# lichten.net
KiCad netlist of a schematic drawn in Altium Designer
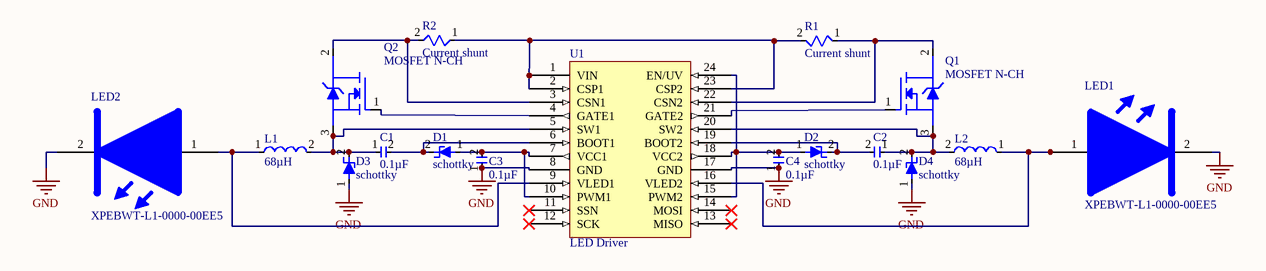
[diagram p0: lichten.SchDoc]

(export (version "E")
  (design (tool "Eeschema 10.0.6"))
  (components
    (comp (ref "C1")
      (value "0.1µF")
      (footprint "RC1206")
      (description "Cap Ceramic 0.1uF 50V X7R 10% SMD 2.0 x 1.2 mm 125 C Paper T/R")
      (fields
        (field (name "MANUFACTURER") "KEMET")
        (field (name "MANUFACTURER PART NUMBER") "C0805C104K5RACTU")
      )
      (libsource (lib "Lichten") (part "C0805C104K5RACTU"))
    )
    (comp (ref "C2")
      (value "0.1µF")
      (footprint "RC1206")
      (description "Cap Ceramic 0.1uF 50V X7R 10% SMD 2.0 x 1.2 mm 125 C Paper T/R")
      (fields
        (field (name "MANUFACTURER") "KEMET")
        (field (name "MANUFACTURER PART NUMBER") "C0805C104K5RACTU")
      )
      (libsource (lib "Lichten") (part "C0805C104K5RACTU"))
    )
    (comp (ref "C3")
      (value "0.1µF")
      (footprint "RC1206")
      (description "Cap Ceramic 0.1uF 50V X7R 10% SMD 2.0 x 1.2 mm 125 C Paper T/R")
      (fields
        (field (name "MANUFACTURER") "KEMET")
        (field (name "MANUFACTURER PART NUMBER") "C0805C104K5RACTU")
      )
      (libsource (lib "Lichten") (part "C0805C104K5RACTU"))
    )
    (comp (ref "C4")
      (value "0.1µF")
      (footprint "RC1206")
      (description "Cap Ceramic 0.1uF 50V X7R 10% SMD 2.0 x 1.2 mm 125 C Paper T/R")
      (fields
        (field (name "MANUFACTURER") "KEMET")
        (field (name "MANUFACTURER PART NUMBER") "C0805C104K5RACTU")
      )
      (libsource (lib "Lichten") (part "C0805C104K5RACTU"))
    )
    (comp (ref "D1")
      (value "schottky")
      (footprint "PMEG3050EP,115")
      (description "NEXPERIA - PMEG3050EP,115 - Schottky-likriktare, 30 V, 5 A, Enkel, SOD-128, 2 Stift, 360 mV")
      (fields
        (field (name "MANUFACTURER") "Nexperia USA")
        (field (name "MANUFACTURER PART NUMBER") "PMEG3050EP,115")
      )
      (libsource (lib "Lichten") (part "PMEG3050EP,115"))
    )
    (comp (ref "D2")
      (value "schottky")
      (footprint "PMEG3050EP,115")
      (description "NEXPERIA - PMEG3050EP,115 - Schottky-likriktare, 30 V, 5 A, Enkel, SOD-128, 2 Stift, 360 mV")
      (fields
        (field (name "MANUFACTURER") "Nexperia USA")
        (field (name "MANUFACTURER PART NUMBER") "PMEG3050EP,115")
      )
      (libsource (lib "Lichten") (part "PMEG3050EP,115"))
    )
    (comp (ref "D3")
      (value "schottky")
      (footprint "PMEG3050EP,115")
      (description "NEXPERIA - PMEG3050EP,115 - Schottky-likriktare, 30 V, 5 A, Enkel, SOD-128, 2 Stift, 360 mV")
      (fields
        (field (name "MANUFACTURER") "Nexperia USA")
        (field (name "MANUFACTURER PART NUMBER") "PMEG3050EP,115")
      )
      (libsource (lib "Lichten") (part "PMEG3050EP,115"))
    )
    (comp (ref "D4")
      (value "schottky")
      (footprint "PMEG3050EP,115")
      (description "NEXPERIA - PMEG3050EP,115 - Schottky-likriktare, 30 V, 5 A, Enkel, SOD-128, 2 Stift, 360 mV")
      (fields
        (field (name "MANUFACTURER") "Nexperia USA")
        (field (name "MANUFACTURER PART NUMBER") "PMEG3050EP,115")
      )
      (libsource (lib "Lichten") (part "PMEG3050EP,115"))
    )
    (comp (ref "L1")
      (value "68µH")
      (footprint "SRR1210-680M")
      (description "BOURNS         SRR1210-680M.             INDUCTOR, SHIELDED, 68UH, 2.7A, SMD")
      (fields (field (name "MANUFACTURER") "Bourns") (field (name "MANUFACTURER PART NUMBER") "SRR1210-680M"))
      (libsource (lib "") (part "SRR1210-680M_1"))
    )
    (comp (ref "L2")
      (value "68µH")
      (footprint "SRR1210-680M")
      (description "BOURNS         SRR1210-680M.             INDUCTOR, SHIELDED, 68UH, 2.7A, SMD")
      (fields (field (name "MANUFACTURER") "Bourns") (field (name "MANUFACTURER PART NUMBER") "SRR1210-680M"))
      (libsource (lib "Lichten") (part "SRR1210-680M"))
    )
    (comp (ref "LED1")
      (value "XPEBWT-L1-0000-00EE5")
      (footprint "XPEBWT-L1-0000-00EE5")
      (description "LED, XLAMP, XP-E, NEUTRAL WHITE, 114LM")
      (fields (field (name "MANUFACTURER") "Cree"))
      (libsource (lib "Lichten") (part "XPEBWT-L1-0000-00EE5"))
    )
    (comp (ref "LED2")
      (value "XPEBWT-L1-0000-00EE5")
      (footprint "XPEBWT-L1-0000-00EE5")
      (description "LED, XLAMP, XP-E, NEUTRAL WHITE, 114LM")
      (fields (field (name "MANUFACTURER") "Cree"))
      (libsource (lib "Lichten") (part "XPEBWT-L1-0000-00EE5"))
    )
    (comp (ref "Q1")
      (value "MOSFET N-CH")
      (footprint "IRLR024NTRPBF - duplicate")
      (description "Trans MOSFET N-CH 55V 17A 3-Pin(2+Tab) DPAK T/R")
      (fields
        (field (name "MANUFACTURER") "International Rectifier")
        (field (name "MANUFACTURER PART NUMBER") "IRLR024NTRPBF")
      )
      (libsource (lib "Lichten") (part "IRLR024NTRPBF"))
    )
    (comp (ref "Q2")
      (value "MOSFET N-CH")
      (footprint "IRLR024NTRPBF - duplicate")
      (description "Trans MOSFET N-CH 55V 17A 3-Pin(2+Tab) DPAK T/R")
      (fields
        (field (name "MANUFACTURER") "International Rectifier")
        (field (name "MANUFACTURER PART NUMBER") "IRLR024NTRPBF")
      )
      (libsource (lib "Lichten") (part "IRLR024NTRPBF"))
    )
    (comp (ref "R1")
      (value "Current shunt")
      (footprint "ERJ-1TRQFR22U")
      (description "Res Thick Film 2512 0.22 Ohm 1% 1W 200ppm/C Molded SMD SMD Embossed Carrier T/R")
      (fields
        (field (name "MANUFACTURER") "Panasonic")
        (field (name "MANUFACTURER PART NUMBER") "ERJ-1TRQFR22U")
      )
      (libsource (lib "Lichten") (part "ERJ-1TRQFR22U"))
    )
    (comp (ref "R2")
      (value "Current shunt")
      (footprint "ERJ-1TRQFR22U")
      (description "Res Thick Film 2512 0.22 Ohm 1% 1W 200ppm/C Molded SMD SMD Embossed Carrier T/R")
      (fields
        (field (name "MANUFACTURER") "Panasonic")
        (field (name "MANUFACTURER PART NUMBER") "ERJ-1TRQFR22U")
      )
      (libsource (lib "Lichten") (part "ERJ-1TRQFR22U"))
    )
    (comp (ref "U1")
      (value "LED Driver")
      (footprint "TPS92518PWPT")
      (description "42-V Dual buck LED controller with SPI interface, analog and PWM dimming 24-HTSSOP -40 to 125")
      (fields
        (field (name "MANUFACTURER") "Texas Instruments")
        (field (name "MANUFACTURER PART NUMBER") "TPS92518PWPT")
      )
      (libsource (lib "Lichten") (part "TPS92518PWPT"))
    )
  )
  (nets
    (net (code "1") (name "GND") (class "Default")
      (node (ref "C3") (pin "1") (pintype "passive"))
      (node (ref "C4") (pin "1") (pintype "passive"))
      (node (ref "D3") (pin "1") (pintype "passive"))
      (node (ref "D4") (pin "1") (pintype "passive"))
      (node (ref "LED1") (pin "2") (pintype "passive"))
      (node (ref "LED2") (pin "2") (pintype "passive"))
      (node (ref "U1") (pin "17") (pinfunction "GND_17") (pintype "power_in"))
      (node (ref "U1") (pin "8") (pinfunction "GND_8") (pintype "power_in"))
    )
    (net (code "2") (name "Net-(Q1-D)") (class "Default")
      (node (ref "Q1") (pin "2") (pinfunction "D_2") (pintype "passive"))
      (node (ref "R1") (pin "1") (pintype "passive"))
      (node (ref "U1") (pin "22") (pinfunction "CSN2_22") (pintype "input"))
    )
    (net (code "3") (name "Net-(Q1-G)") (class "Default")
      (node (ref "Q1") (pin "1") (pinfunction "G_1") (pintype "passive"))
      (node (ref "U1") (pin "21") (pinfunction "GATE2_21") (pintype "output"))
    )
    (net (code "4") (name "Net-(Q1-S)") (class "Default")
      (node (ref "C2") (pin "1") (pintype "passive"))
      (node (ref "D4") (pin "2") (pintype "passive"))
      (node (ref "L2") (pin "2") (pintype "passive"))
      (node (ref "Q1") (pin "3") (pinfunction "S_3") (pintype "passive"))
      (node (ref "U1") (pin "20") (pinfunction "SW2_20") (pintype "input"))
    )
    (net (code "5") (name "Net-(Q2-D)") (class "Default")
      (node (ref "Q2") (pin "2") (pinfunction "D_2") (pintype "passive"))
      (node (ref "R2") (pin "2") (pinfunction "2_2") (pintype "passive"))
      (node (ref "U1") (pin "3") (pinfunction "CSN1_3") (pintype "input"))
    )
    (net (code "6") (name "Net-(Q2-G)") (class "Default")
      (node (ref "Q2") (pin "1") (pinfunction "G_1") (pintype "passive"))
      (node (ref "U1") (pin "4") (pinfunction "GATE1_4") (pintype "output"))
    )
    (net (code "7") (name "Net-(Q2-S)") (class "Default")
      (node (ref "C1") (pin "1") (pintype "passive"))
      (node (ref "D3") (pin "2") (pintype "passive"))
      (node (ref "L1") (pin "2") (pintype "passive"))
      (node (ref "Q2") (pin "3") (pinfunction "S_3") (pintype "passive"))
      (node (ref "U1") (pin "5") (pinfunction "SW1_5") (pintype "input"))
    )
    (net (code "8") (name "Net-(U1-BOOT1)") (class "Default")
      (node (ref "C1") (pin "2") (pintype "passive"))
      (node (ref "D1") (pin "2") (pintype "passive"))
      (node (ref "U1") (pin "6") (pinfunction "BOOT1_6") (pintype "input"))
    )
    (net (code "9") (name "Net-(U1-BOOT2)") (class "Default")
      (node (ref "C2") (pin "2") (pintype "passive"))
      (node (ref "D2") (pin "2") (pintype "passive"))
      (node (ref "U1") (pin "19") (pinfunction "BOOT2_19") (pintype "input"))
    )
    (net (code "10") (name "Net-(U1-CSP1)") (class "Default")
      (node (ref "R1") (pin "2") (pinfunction "2_2") (pintype "passive"))
      (node (ref "R2") (pin "1") (pintype "passive"))
      (node (ref "U1") (pin "1") (pinfunction "VIN_1") (pintype "power_in"))
      (node (ref "U1") (pin "2") (pinfunction "CSP1_2") (pintype "input"))
      (node (ref "U1") (pin "23") (pinfunction "CSP2_23") (pintype "input"))
    )
    (net (code "11") (name "Net-(U1-EN{slash}UV)") (class "Default")
      (node (ref "C4") (pin "2") (pintype "passive"))
      (node (ref "D2") (pin "1") (pintype "passive"))
      (node (ref "U1") (pin "15") (pinfunction "PWM2_15") (pintype "input"))
      (node (ref "U1") (pin "18") (pinfunction "VCC2_18") (pintype "output"))
      (node (ref "U1") (pin "24") (pinfunction "EN/UV_24") (pintype "input"))
    )
    (net (code "12") (name "Net-(U1-PWM1)") (class "Default")
      (node (ref "C3") (pin "2") (pintype "passive"))
      (node (ref "D1") (pin "1") (pintype "passive"))
      (node (ref "U1") (pin "10") (pinfunction "PWM1_10") (pintype "input"))
      (node (ref "U1") (pin "7") (pinfunction "VCC1_7") (pintype "output"))
    )
    (net (code "13") (name "Net-(U1-VLED1)") (class "Default")
      (node (ref "L1") (pin "1") (pintype "passive"))
      (node (ref "LED2") (pin "1") (pintype "passive"))
      (node (ref "U1") (pin "9") (pinfunction "VLED1_9") (pintype "input"))
    )
    (net (code "14") (name "Net-(U1-VLED2)") (class "Default")
      (node (ref "L2") (pin "1") (pintype "passive"))
      (node (ref "LED1") (pin "1") (pintype "passive"))
      (node (ref "U1") (pin "16") (pinfunction "VLED2_16") (pintype "input"))
    )
    (net (code "15") (name "unconnected-(U1-MISO-Pad13)") (class "Default")
      (node (ref "U1") (pin "13") (pinfunction "MISO_13") (pintype "input+no_connect"))
    )
    (net (code "16") (name "unconnected-(U1-MOSI-Pad14)") (class "Default")
      (node (ref "U1") (pin "14") (pinfunction "MOSI_14") (pintype "input+no_connect"))
    )
    (net (code "17") (name "unconnected-(U1-SCK-Pad12)") (class "Default")
      (node (ref "U1") (pin "12") (pinfunction "SCK_12") (pintype "input+no_connect"))
    )
    (net (code "18") (name "unconnected-(U1-SSN-Pad11)") (class "Default")
      (node (ref "U1") (pin "11") (pinfunction "SSN_11") (pintype "input+no_connect"))
    )
  )
)
